# FPGA_config.net
KiCad netlist of a schematic drawn in Altium Designer
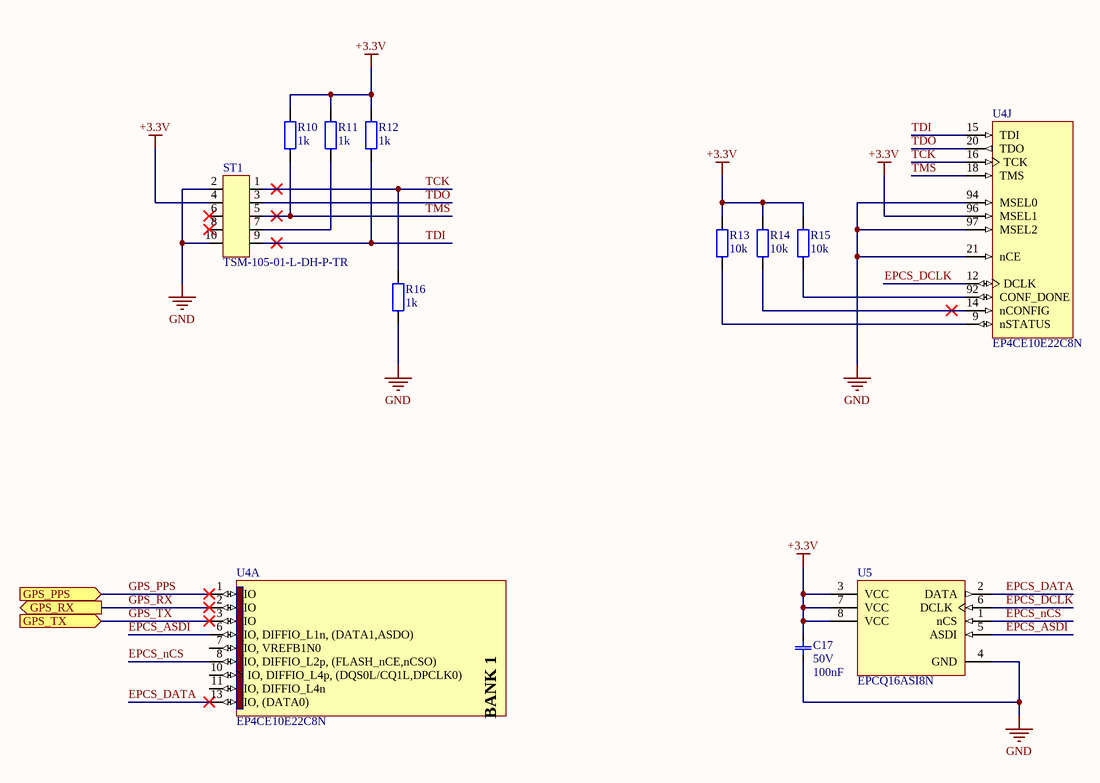
[diagram p0: FPGA_config.SchDoc]

(export (version "E")
  (design (tool "Eeschema 10.0.6"))
  (components
    (comp (ref "C17")
      (value "100nF")
      (footprint "MLCC_0603")
      (description "MLCC 100nF 50V 0603")
      (fields (field (name "VOLTAGE") "50V"))
      (libsource (lib "Nixie") (part "MLCC 100nF 50V 0603"))
    )
    (comp (ref "R10")
      (value "1k")
      (footprint "RES0805")
      (description "Chip resistor 1k 0805")
      (libsource (lib "Nixie") (part "1k 0805"))
    )
    (comp (ref "R11")
      (value "1k")
      (footprint "RES0805")
      (description "Chip resistor 1k 0805")
      (libsource (lib "Nixie") (part "1k 0805"))
    )
    (comp (ref "R12")
      (value "1k")
      (footprint "RES0805")
      (description "Chip resistor 1k 0805")
      (libsource (lib "Nixie") (part "1k 0805"))
    )
    (comp (ref "R13")
      (value "10k")
      (footprint "RES0805")
      (description "Chip resistor 10k 0805")
      (libsource (lib "Nixie") (part "10k 0805"))
    )
    (comp (ref "R14")
      (value "10k")
      (footprint "RES0805")
      (description "Chip resistor 10k 0805")
      (libsource (lib "Nixie") (part "10k 0805"))
    )
    (comp (ref "R15")
      (value "10k")
      (footprint "RES0805")
      (description "Chip resistor 10k 0805")
      (libsource (lib "Nixie") (part "10k 0805"))
    )
    (comp (ref "R16")
      (value "1k")
      (footprint "RES0805")
      (description "Chip resistor 1k 0805")
      (libsource (lib "Nixie") (part "1k 0805"))
    )
    (comp (ref "ST1")
      (value "TSM-105-01-L-DH-P-TR")
      (footprint "TSM-105-01-L-DH-P-TR")
      (description "Male Connector, 2x5 pins, 2.54 mm, right angle")
      (fields
        (field (name "PART_NUMBER") "TSM-105-01-L-DH-P")
        (field (name "A2000_PART_NUMBER") "06.02.0061")
      )
      (libsource (lib "Nixie") (part "TSM-105-01-L-DH-P-TR"))
    )
    (comp (ref "U4")
      (value "EP4CE10E22C8N")
      (footprint "EP4CE10E22C8N")
      (fields (field (name "MANUFACTURER") "Altera"))
      (libsource (lib "Nixie") (part "EP4CE10E22C8N"))
    )
    (comp (ref "U5")
      (value "EPCQ16ASI8N")
      (footprint "EPCQ16ASI8N")
      (libsource (lib "Nixie") (part "EPCQ16ASI8N"))
    )
  )
  (nets
    (net (code "1") (name "+3.3V") (class "Default")
      (node (ref "C17") (pin "2") (pinfunction "2_2") (pintype "passive"))
      (node (ref "R10") (pin "2") (pinfunction "2_2") (pintype "passive"))
      (node (ref "R11") (pin "2") (pinfunction "2_2") (pintype "passive"))
      (node (ref "R12") (pin "2") (pinfunction "2_2") (pintype "passive"))
      (node (ref "R13") (pin "2") (pinfunction "2_2") (pintype "passive"))
      (node (ref "R14") (pin "2") (pinfunction "2_2") (pintype "passive"))
      (node (ref "R15") (pin "2") (pinfunction "2_2") (pintype "passive"))
      (node (ref "ST1") (pin "4") (pintype "passive"))
      (node (ref "U4") (pin "96") (pinfunction "MSEL1_96") (pintype "input"))
      (node (ref "U5") (pin "3") (pinfunction "VCC_3") (pintype "power_in"))
      (node (ref "U5") (pin "7") (pinfunction "VCC_7") (pintype "power_in"))
      (node (ref "U5") (pin "8") (pinfunction "VCC_8") (pintype "power_in"))
    )
    (net (code "2") (name "/EPCS_ASDI") (class "Default")
      (node (ref "U4") (pin "6") (pinfunction "IO,_DIFFIO_L1n,_(DATA1,ASDO)_6") (pintype "bidirectional"))
      (node (ref "U5") (pin "5") (pinfunction "ASDI_5") (pintype "input"))
    )
    (net (code "3") (name "/EPCS_DATA") (class "Default")
      (node (ref "U4") (pin "13") (pinfunction "IO,_(DATA0)_13") (pintype "bidirectional"))
      (node (ref "U5") (pin "2") (pinfunction "DATA_2") (pintype "output"))
    )
    (net (code "4") (name "/EPCS_DCLK") (class "Default")
      (node (ref "U4") (pin "12") (pinfunction "DCLK_12") (pintype "bidirectional"))
      (node (ref "U5") (pin "6") (pinfunction "DCLK_6") (pintype "input"))
    )
    (net (code "5") (name "/EPCS_nCS") (class "Default")
      (node (ref "U4") (pin "8") (pinfunction "IO,_DIFFIO_L2p,_(FLASH_nCE,nCSO)_8") (pintype "bidirectional"))
      (node (ref "U5") (pin "1") (pinfunction "nCS_1") (pintype "input"))
    )
    (net (code "6") (name "/GPS_PPS") (class "Default")
      (node (ref "U4") (pin "1") (pinfunction "IO_1") (pintype "bidirectional+no_connect"))
    )
    (net (code "7") (name "/GPS_RX") (class "Default")
      (node (ref "U4") (pin "2") (pinfunction "IO_2") (pintype "bidirectional+no_connect"))
    )
    (net (code "8") (name "/GPS_TX") (class "Default")
      (node (ref "U4") (pin "3") (pinfunction "IO_3") (pintype "bidirectional+no_connect"))
    )
    (net (code "9") (name "/TCK") (class "Default")
      (node (ref "R16") (pin "2") (pinfunction "2_2") (pintype "passive"))
      (node (ref "ST1") (pin "1") (pintype "passive"))
      (node (ref "U4") (pin "16") (pinfunction "TCK_16") (pintype "input"))
    )
    (net (code "10") (name "/TDI") (class "Default")
      (node (ref "R12") (pin "1") (pinfunction "1_1") (pintype "passive"))
      (node (ref "ST1") (pin "9") (pintype "passive"))
      (node (ref "U4") (pin "15") (pinfunction "TDI_15") (pintype "input"))
    )
    (net (code "11") (name "/TDO") (class "Default")
      (node (ref "ST1") (pin "3") (pintype "passive"))
      (node (ref "U4") (pin "20") (pinfunction "TDO_20") (pintype "output"))
    )
    (net (code "12") (name "/TMS") (class "Default")
      (node (ref "R10") (pin "1") (pinfunction "1_1") (pintype "passive"))
      (node (ref "ST1") (pin "5") (pintype "passive"))
      (node (ref "U4") (pin "18") (pinfunction "TMS_18") (pintype "input"))
    )
    (net (code "13") (name "GND") (class "Default")
      (node (ref "C17") (pin "1") (pinfunction "1_1") (pintype "passive"))
      (node (ref "R16") (pin "1") (pinfunction "1_1") (pintype "passive"))
      (node (ref "ST1") (pin "10") (pintype "passive"))
      (node (ref "ST1") (pin "2") (pintype "passive"))
      (node (ref "U4") (pin "21") (pinfunction "nCE_21") (pintype "input"))
      (node (ref "U4") (pin "94") (pinfunction "MSEL0_94") (pintype "input"))
      (node (ref "U4") (pin "97") (pinfunction "MSEL2_97") (pintype "input"))
      (node (ref "U5") (pin "4") (pinfunction "GND_4") (pintype "power_in"))
    )
    (net (code "14") (name "Net-(R11-Pad1)") (class "Default")
      (node (ref "R11") (pin "1") (pinfunction "1_1") (pintype "passive"))
      (node (ref "ST1") (pin "7") (pintype "passive"))
    )
    (net (code "15") (name "Net-(U4J-CONF_DONE)") (class "Default")
      (node (ref "R15") (pin "1") (pinfunction "1_1") (pintype "passive"))
      (node (ref "U4") (pin "92") (pinfunction "CONF_DONE_92") (pintype "bidirectional"))
    )
    (net (code "16") (name "Net-(U4J-nCONFIG)") (class "Default")
      (node (ref "R14") (pin "1") (pinfunction "1_1") (pintype "passive"))
      (node (ref "U4") (pin "14") (pinfunction "nCONFIG_14") (pintype "input"))
    )
    (net (code "17") (name "Net-(U4J-nSTATUS)") (class "Default")
      (node (ref "R13") (pin "1") (pinfunction "1_1") (pintype "passive"))
      (node (ref "U4") (pin "9") (pinfunction "nSTATUS_9") (pintype "bidirectional"))
    )
    (net (code "18") (name "unconnected-(ST1-Pad6)") (class "Default")
      (node (ref "ST1") (pin "6") (pintype "passive+no_connect"))
    )
    (net (code "19") (name "unconnected-(ST1-Pad8)") (class "Default")
      (node (ref "ST1") (pin "8") (pintype "passive+no_connect"))
    )
    (net (code "20") (name "unconnected-(U4A-IO,_DIFFIO_L4n-Pad11)") (class "Default")
      (node (ref "U4") (pin "11") (pinfunction "IO,_DIFFIO_L4n_11") (pintype "bidirectional"))
    )
    (net (code "21") (name "unconnected-(U4A-IO,_DIFFIO_L4p,_(DQS0L{slash}CQ1L,DPCLK0)-Pad10)") (class "Default")
      (node (ref "U4") (pin "10") (pinfunction "IO,_DIFFIO_L4p,_(DQS0L/CQ1L,DPCLK0)_10") (pintype "bidirectional"))
    )
    (net (code "22") (name "unconnected-(U4A-IO,_VREFB1N0-Pad7)") (class "Default")
      (node (ref "U4") (pin "7") (pinfunction "IO,_VREFB1N0_7") (pintype "bidirectional"))
    )
  )
)
